# ZHSD-USB-UART.net
KiCad netlist of a schematic drawn in Altium Designer
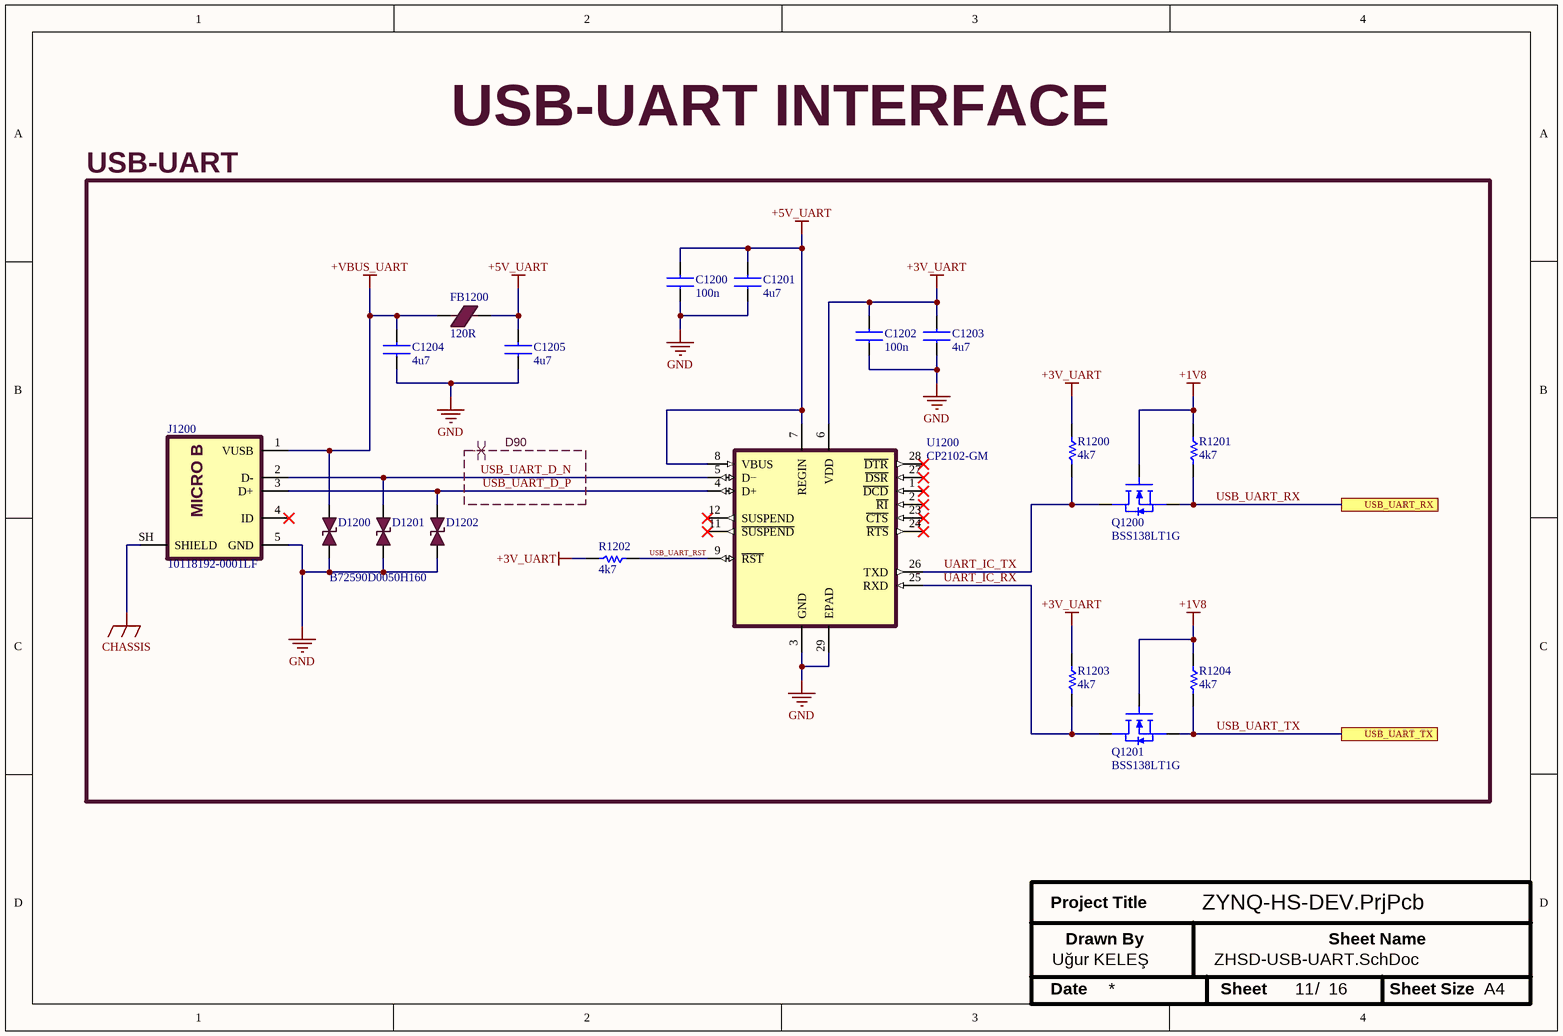
[diagram p0: ZHSD-USB-UART.SchDoc]

(export (version "E")
  (design (tool "Eeschema 10.0.6"))
  (components
    (comp (ref "C1200")
      (value "100n")
      (footprint "0603CAPC1608X09N")
      (description "CAP CER 0.1UF 16V X7R 0402 (1005) ±10%")
      (fields (field (name "MANUFACTURER") "Murata Electronics") (field (name "MPN") "GRM155R71C104KA88J"))
      (libsource (lib "UK_Library") (part "GRM155R71C104KA88J"))
    )
    (comp (ref "C1201")
      (value "4u7")
      (footprint "0603CAPC1608X09N")
      (description "CAP CER 4.7UF 10V X5R 0603 (1608) ±10%")
      (fields
        (field (name "MANUFACTURER") "Samsung Electro-Mechanics")
        (field (name "MPN") "CL10A475KP8NNNC")
      )
      (libsource (lib "UK_Library") (part "CL10A475KP8NNNC"))
    )
    (comp (ref "C1202")
      (value "100n")
      (footprint "0603CAPC1608X09N")
      (description "CAP CER 0.1UF 16V X7R 0402 (1005) ±10%")
      (fields (field (name "MANUFACTURER") "Murata Electronics") (field (name "MPN") "GRM155R71C104KA88J"))
      (libsource (lib "UK_Library") (part "GRM155R71C104KA88J"))
    )
    (comp (ref "C1203")
      (value "4u7")
      (footprint "0603CAPC1608X09N")
      (description "CAP CER 4.7UF 10V X5R 0603 (1608) ±10%")
      (fields
        (field (name "MANUFACTURER") "Samsung Electro-Mechanics")
        (field (name "MPN") "CL10A475KP8NNNC")
      )
      (libsource (lib "UK_Library") (part "CL10A475KP8NNNC"))
    )
    (comp (ref "C1204")
      (value "4u7")
      (footprint "0603CAPC1608X09N")
      (description "CAP CER 4.7UF 10V X5R 0603 (1608) ±10%")
      (fields
        (field (name "MANUFACTURER") "Samsung Electro-Mechanics")
        (field (name "MPN") "CL10A475KP8NNNC")
      )
      (libsource (lib "UK_Library") (part "CL10A475KP8NNNC"))
    )
    (comp (ref "C1205")
      (value "4u7")
      (footprint "0603CAPC1608X09N")
      (description "CAP CER 4.7UF 10V X5R 0603 (1608) ±10%")
      (fields
        (field (name "MANUFACTURER") "Samsung Electro-Mechanics")
        (field (name "MPN") "CL10A475KP8NNNC")
      )
      (libsource (lib "UK_Library") (part "CL10A475KP8NNNC"))
    )
    (comp (ref "D1200")
      (value "B72590D0050H160")
      (footprint "0402DIOC1005X06N")
      (description "Varistor 1 Circuit Surface Mount, MLCV 0402 (1005 Metric)")
      (fields (field (name "MANUFACTURER") "EPCOS - TDK Electronics"))
      (libsource (lib "UK_Library") (part "B72590D0050H160"))
    )
    (comp (ref "D1201")
      (value "B72590D0050H160")
      (footprint "0402DIOC1005X06N")
      (description "Varistor 1 Circuit Surface Mount, MLCV 0402 (1005 Metric)")
      (fields (field (name "MANUFACTURER") "EPCOS - TDK Electronics"))
      (libsource (lib "UK_Library") (part "B72590D0050H160"))
    )
    (comp (ref "D1202")
      (value "B72590D0050H160")
      (footprint "0402DIOC1005X06N")
      (description "Varistor 1 Circuit Surface Mount, MLCV 0402 (1005 Metric)")
      (fields (field (name "MANUFACTURER") "EPCOS - TDK Electronics"))
      (libsource (lib "UK_Library") (part "B72590D0050H160"))
    )
    (comp (ref "FB1200")
      (value "120R")
      (footprint "0603INDC1608X08N")
      (description "FERRITE BEAD 120 OHM 0603 (1608) 3A 25mOhm")
      (fields (field (name "MANUFACTURER") "Murata Electronics") (field (name "MPN") "BLM18SG121TN1D"))
      (libsource (lib "UK_Library") (part "BLM18SG121TN1D"))
    )
    (comp (ref "J1200")
      (value "10118192-0001LF")
      (footprint "USB2.0 MICRO B SMD")
      (description "CONN RCPT USB2.0 MICRO B SMD R/A")
      (fields (field (name "MANUFACTURER") "Amphenol ICC (FCI)"))
      (libsource (lib "UK_Library") (part "USB-MICRO-B"))
    )
    (comp (ref "Q1200")
      (value "BSS138LT1G")
      (footprint "SOT95P237X89-3N")
      (description "N-Channel 50 V 200mA (Ta) 225mW (Ta) Surface Mount SOT-23-3 (TO-236)")
      (fields (field (name "MANUFACTURER") "onsemi"))
      (libsource (lib "UK_Library") (part "BSS138LT1G"))
    )
    (comp (ref "Q1201")
      (value "BSS138LT1G")
      (footprint "SOT95P237X89-3N")
      (description "N-Channel 50 V 200mA (Ta) 225mW (Ta) Surface Mount SOT-23-3 (TO-236)")
      (fields (field (name "MANUFACTURER") "onsemi"))
      (libsource (lib "UK_Library") (part "BSS138LT1G"))
    )
    (comp (ref "R1200")
      (value "4k7")
      (footprint "0402RESC1005X04N")
      (description "RES 4.7K OHM 5% 1/16W 0402 (1005)")
      (fields (field (name "MANUFACTURER") "YAGEO") (field (name "MPN") "RT0402FRE0780RL"))
      (libsource (lib "UK_Library") (part "RC0402JR-074K7L"))
    )
    (comp (ref "R1201")
      (value "4k7")
      (footprint "0402RESC1005X04N")
      (description "RES 4.7K OHM 5% 1/16W 0402 (1005)")
      (fields (field (name "MANUFACTURER") "YAGEO") (field (name "MPN") "RT0402FRE0780RL"))
      (libsource (lib "UK_Library") (part "RC0402JR-074K7L"))
    )
    (comp (ref "R1202")
      (value "4k7")
      (footprint "0402RESC1005X04N")
      (description "RES 4.7K OHM 5% 1/16W 0402 (1005)")
      (fields (field (name "MANUFACTURER") "YAGEO") (field (name "MPN") "RT0402FRE0780RL"))
      (libsource (lib "UK_Library") (part "RC0402JR-074K7L"))
    )
    (comp (ref "R1203")
      (value "4k7")
      (footprint "0402RESC1005X04N")
      (description "RES 4.7K OHM 5% 1/16W 0402 (1005)")
      (fields (field (name "MANUFACTURER") "YAGEO") (field (name "MPN") "RT0402FRE0780RL"))
      (libsource (lib "UK_Library") (part "RC0402JR-074K7L"))
    )
    (comp (ref "R1204")
      (value "4k7")
      (footprint "0402RESC1005X04N")
      (description "RES 4.7K OHM 5% 1/16W 0402 (1005)")
      (fields (field (name "MANUFACTURER") "YAGEO") (field (name "MPN") "RT0402FRE0780RL"))
      (libsource (lib "UK_Library") (part "RC0402JR-074K7L"))
    )
    (comp (ref "U1200")
      (value "CP2102-GM")
      (footprint "QFN50P500X500X100_HS-29N")
      (description "USB Bridge, USB to UART USB 2.0 UART Interface 28-QFN (5x5)")
      (fields (field (name "MANUFACTURER") "Silicon Labs"))
      (libsource (lib "UK_Library_SCH") (part "CP2102-GM"))
    )
  )
  (nets
    (net (code "1") (name "+1V8") (class "Default")
      (node (ref "Q1200") (pin "1") (pinfunction "G_1") (pintype "passive"))
      (node (ref "Q1201") (pin "1") (pinfunction "G_1") (pintype "passive"))
      (node (ref "R1201") (pin "1") (pinfunction "1_1") (pintype "passive"))
      (node (ref "R1204") (pin "1") (pinfunction "1_1") (pintype "passive"))
    )
    (net (code "2") (name "+3V_UART") (class "Default")
      (node (ref "C1202") (pin "2") (pinfunction "2_2") (pintype "passive"))
      (node (ref "C1203") (pin "2") (pinfunction "2_2") (pintype "passive"))
      (node (ref "R1200") (pin "1") (pinfunction "1_1") (pintype "passive"))
      (node (ref "R1202") (pin "2") (pinfunction "2_2") (pintype "passive"))
      (node (ref "R1203") (pin "1") (pinfunction "1_1") (pintype "passive"))
      (node (ref "U1200") (pin "6") (pinfunction "VDD_6") (pintype "power_in"))
    )
    (net (code "3") (name "+5V_UART") (class "Default")
      (node (ref "C1200") (pin "2") (pinfunction "2_2") (pintype "passive"))
      (node (ref "C1201") (pin "2") (pinfunction "2_2") (pintype "passive"))
      (node (ref "C1205") (pin "2") (pinfunction "2_2") (pintype "passive"))
      (node (ref "FB1200") (pin "2") (pinfunction "2_2") (pintype "passive"))
      (node (ref "U1200") (pin "7") (pinfunction "REGIN_7") (pintype "power_in"))
      (node (ref "U1200") (pin "8") (pinfunction "VBUS_8") (pintype "input"))
    )
    (net (code "4") (name "+VBUS_UART") (class "Default")
      (node (ref "C1204") (pin "2") (pinfunction "2_2") (pintype "passive"))
      (node (ref "D1200") (pin "2") (pinfunction "2_2") (pintype "passive"))
      (node (ref "FB1200") (pin "1") (pinfunction "1_1") (pintype "passive"))
      (node (ref "J1200") (pin "1") (pinfunction "VUSB_1") (pintype "passive"))
    )
    (net (code "5") (name "/UART_IC_RX") (class "Default")
      (node (ref "Q1201") (pin "3") (pinfunction "D_3") (pintype "passive"))
      (node (ref "R1203") (pin "2") (pinfunction "2_2") (pintype "passive"))
      (node (ref "U1200") (pin "25") (pinfunction "RXD_25") (pintype "input"))
    )
    (net (code "6") (name "/UART_IC_TX") (class "Default")
      (node (ref "Q1200") (pin "3") (pinfunction "D_3") (pintype "passive"))
      (node (ref "R1200") (pin "2") (pinfunction "2_2") (pintype "passive"))
      (node (ref "U1200") (pin "26") (pinfunction "TXD_26") (pintype "output"))
    )
    (net (code "7") (name "/USB_UART_D_N") (class "Default")
      (node (ref "D1201") (pin "2") (pinfunction "2_2") (pintype "passive"))
      (node (ref "J1200") (pin "2") (pinfunction "D-_2") (pintype "passive"))
      (node (ref "U1200") (pin "5") (pinfunction "D−_5") (pintype "bidirectional"))
    )
    (net (code "8") (name "/USB_UART_D_P") (class "Default")
      (node (ref "D1202") (pin "2") (pinfunction "2_2") (pintype "passive"))
      (node (ref "J1200") (pin "3") (pinfunction "D+_3") (pintype "passive"))
      (node (ref "U1200") (pin "4") (pinfunction "D+_4") (pintype "bidirectional"))
    )
    (net (code "9") (name "/USB_UART_RST") (class "Default")
      (node (ref "R1202") (pin "1") (pinfunction "1_1") (pintype "passive"))
      (node (ref "U1200") (pin "9") (pinfunction "RST_9") (pintype "bidirectional"))
    )
    (net (code "10") (name "/USB_UART_RX") (class "Default")
      (node (ref "Q1200") (pin "2") (pinfunction "S_2") (pintype "passive"))
      (node (ref "R1201") (pin "2") (pinfunction "2_2") (pintype "passive"))
    )
    (net (code "11") (name "/USB_UART_TX") (class "Default")
      (node (ref "Q1201") (pin "2") (pinfunction "S_2") (pintype "passive"))
      (node (ref "R1204") (pin "2") (pinfunction "2_2") (pintype "passive"))
    )
    (net (code "12") (name "CHASSIS") (class "Default")
      (node (ref "J1200") (pin "SH") (pinfunction "SHIELD_SH") (pintype "passive"))
    )
    (net (code "13") (name "GND") (class "Default")
      (node (ref "C1200") (pin "1") (pinfunction "1_1") (pintype "passive"))
      (node (ref "C1201") (pin "1") (pinfunction "1_1") (pintype "passive"))
      (node (ref "C1202") (pin "1") (pinfunction "1_1") (pintype "passive"))
      (node (ref "C1203") (pin "1") (pinfunction "1_1") (pintype "passive"))
      (node (ref "C1204") (pin "1") (pinfunction "1_1") (pintype "passive"))
      (node (ref "C1205") (pin "1") (pinfunction "1_1") (pintype "passive"))
      (node (ref "D1200") (pin "1") (pinfunction "1_1") (pintype "passive"))
      (node (ref "D1201") (pin "1") (pinfunction "1_1") (pintype "passive"))
      (node (ref "D1202") (pin "1") (pinfunction "1_1") (pintype "passive"))
      (node (ref "J1200") (pin "5") (pinfunction "GND_5") (pintype "passive"))
      (node (ref "U1200") (pin "29") (pinfunction "EPAD_29") (pintype "power_in"))
      (node (ref "U1200") (pin "3") (pinfunction "GND_3") (pintype "power_in"))
    )
    (net (code "14") (name "unconnected-(J1200-ID-Pad4)") (class "Default")
      (node (ref "J1200") (pin "4") (pinfunction "ID_4") (pintype "passive+no_connect"))
    )
    (net (code "15") (name "unconnected-(U1200-CTS-Pad23)") (class "Default")
      (node (ref "U1200") (pin "23") (pinfunction "CTS_23") (pintype "input+no_connect"))
    )
    (net (code "16") (name "unconnected-(U1200-DCD-Pad1)") (class "Default")
      (node (ref "U1200") (pin "1") (pinfunction "DCD_1") (pintype "input+no_connect"))
    )
    (net (code "17") (name "unconnected-(U1200-DSR-Pad27)") (class "Default")
      (node (ref "U1200") (pin "27") (pinfunction "DSR_27") (pintype "input+no_connect"))
    )
    (net (code "18") (name "unconnected-(U1200-DTR-Pad28)") (class "Default")
      (node (ref "U1200") (pin "28") (pinfunction "DTR_28") (pintype "output+no_connect"))
    )
    (net (code "19") (name "unconnected-(U1200-RI-Pad2)") (class "Default")
      (node (ref "U1200") (pin "2") (pinfunction "RI_2") (pintype "input+no_connect"))
    )
    (net (code "20") (name "unconnected-(U1200-RTS-Pad24)") (class "Default")
      (node (ref "U1200") (pin "24") (pinfunction "RTS_24") (pintype "output+no_connect"))
    )
    (net (code "21") (name "unconnected-(U1200-SUSPEND-Pad11)") (class "Default")
      (node (ref "U1200") (pin "11") (pinfunction "SUSPEND_11") (pintype "output+no_connect"))
    )
    (net (code "22") (name "unconnected-(U1200-SUSPEND-Pad12)") (class "Default")
      (node (ref "U1200") (pin "12") (pinfunction "SUSPEND_12") (pintype "output+no_connect"))
    )
  )
)
